# Sega_Master_System_Quick_Solder_BIOS_v1p.net
KiCad netlist of a schematic drawn in EAGLE
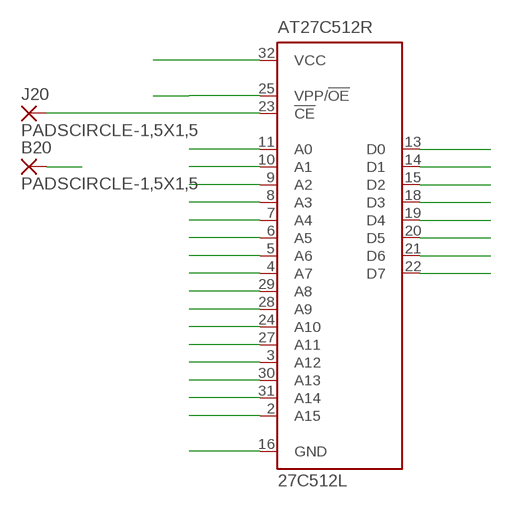
[diagram p0: schematic, sheet 1]

(export (version "E")
  (design (tool "Eeschema 10.0.6"))
  (components
    (comp (ref "AT27C512R")
      (value "27C512L")
      (footprint "eagle-import:PLCC-32")
      (fields (field (name "MPN") "M27C512-90C1"))
      (libsource (lib "eagle-import") (part "27512LC"))
    )
    (comp (ref "B20")
      (value "PADSCIRCLE-1,5X1,5")
      (footprint "eagle-import:CIRCLE-1,5X1,5")
      (libsource (lib "eagle-import") (part "PADSCIRCLE-1,5X1,5"))
    )
    (comp (ref "J20")
      (value "PADSCIRCLE-1,5X1,5")
      (footprint "eagle-import:CIRCLE-1,5X1,5")
      (libsource (lib "eagle-import") (part "PADSCIRCLE-1,5X1,5"))
    )
  )
  (nets
    (net (code "1") (name "Net-(AT27C512R-~{CE})") (class "Default")
      (node (ref "AT27C512R") (pin "23") (pinfunction "~{CE}_23") (pintype "input"))
      (node (ref "J20") (pin "1") (pinfunction "P_1") (pintype "passive"))
    )
    (net (code "2") (name "unconnected-(AT27C512R-A0-Pad11)") (class "Default")
      (node (ref "AT27C512R") (pin "11") (pinfunction "A0_11") (pintype "input"))
    )
    (net (code "3") (name "unconnected-(AT27C512R-A1-Pad10)") (class "Default")
      (node (ref "AT27C512R") (pin "10") (pinfunction "A1_10") (pintype "input"))
    )
    (net (code "4") (name "unconnected-(AT27C512R-A2-Pad9)") (class "Default")
      (node (ref "AT27C512R") (pin "9") (pinfunction "A2_9") (pintype "input"))
    )
    (net (code "5") (name "unconnected-(AT27C512R-A3-Pad8)") (class "Default")
      (node (ref "AT27C512R") (pin "8") (pinfunction "A3_8") (pintype "input"))
    )
    (net (code "6") (name "unconnected-(AT27C512R-A4-Pad7)") (class "Default")
      (node (ref "AT27C512R") (pin "7") (pinfunction "A4_7") (pintype "input"))
    )
    (net (code "7") (name "unconnected-(AT27C512R-A5-Pad6)") (class "Default")
      (node (ref "AT27C512R") (pin "6") (pinfunction "A5_6") (pintype "input"))
    )
    (net (code "8") (name "unconnected-(AT27C512R-A6-Pad5)") (class "Default")
      (node (ref "AT27C512R") (pin "5") (pinfunction "A6_5") (pintype "input"))
    )
    (net (code "9") (name "unconnected-(AT27C512R-A7-Pad4)") (class "Default")
      (node (ref "AT27C512R") (pin "4") (pinfunction "A7_4") (pintype "input"))
    )
    (net (code "10") (name "unconnected-(AT27C512R-A8-Pad29)") (class "Default")
      (node (ref "AT27C512R") (pin "29") (pinfunction "A8_29") (pintype "input"))
    )
    (net (code "11") (name "unconnected-(AT27C512R-A9-Pad28)") (class "Default")
      (node (ref "AT27C512R") (pin "28") (pinfunction "A9_28") (pintype "input"))
    )
    (net (code "12") (name "unconnected-(AT27C512R-A10-Pad24)") (class "Default")
      (node (ref "AT27C512R") (pin "24") (pinfunction "A10_24") (pintype "input"))
    )
    (net (code "13") (name "unconnected-(AT27C512R-A11-Pad27)") (class "Default")
      (node (ref "AT27C512R") (pin "27") (pinfunction "A11_27") (pintype "input"))
    )
    (net (code "14") (name "unconnected-(AT27C512R-A12-Pad3)") (class "Default")
      (node (ref "AT27C512R") (pin "3") (pinfunction "A12_3") (pintype "input"))
    )
    (net (code "15") (name "unconnected-(AT27C512R-A13-Pad30)") (class "Default")
      (node (ref "AT27C512R") (pin "30") (pinfunction "A13_30") (pintype "input"))
    )
    (net (code "16") (name "unconnected-(AT27C512R-A14-Pad31)") (class "Default")
      (node (ref "AT27C512R") (pin "31") (pinfunction "A14_31") (pintype "input"))
    )
    (net (code "17") (name "unconnected-(AT27C512R-A15-Pad2)") (class "Default")
      (node (ref "AT27C512R") (pin "2") (pinfunction "A15_2") (pintype "input"))
    )
    (net (code "18") (name "unconnected-(AT27C512R-D0-Pad13)") (class "Default")
      (node (ref "AT27C512R") (pin "13") (pinfunction "D0_13") (pintype "tri_state"))
    )
    (net (code "19") (name "unconnected-(AT27C512R-D1-Pad14)") (class "Default")
      (node (ref "AT27C512R") (pin "14") (pinfunction "D1_14") (pintype "tri_state"))
    )
    (net (code "20") (name "unconnected-(AT27C512R-D2-Pad15)") (class "Default")
      (node (ref "AT27C512R") (pin "15") (pinfunction "D2_15") (pintype "tri_state"))
    )
    (net (code "21") (name "unconnected-(AT27C512R-D3-Pad18)") (class "Default")
      (node (ref "AT27C512R") (pin "18") (pinfunction "D3_18") (pintype "tri_state"))
    )
    (net (code "22") (name "unconnected-(AT27C512R-D4-Pad19)") (class "Default")
      (node (ref "AT27C512R") (pin "19") (pinfunction "D4_19") (pintype "tri_state"))
    )
    (net (code "23") (name "unconnected-(AT27C512R-D5-Pad20)") (class "Default")
      (node (ref "AT27C512R") (pin "20") (pinfunction "D5_20") (pintype "tri_state"))
    )
    (net (code "24") (name "unconnected-(AT27C512R-D6-Pad21)") (class "Default")
      (node (ref "AT27C512R") (pin "21") (pinfunction "D6_21") (pintype "tri_state"))
    )
    (net (code "25") (name "unconnected-(AT27C512R-D7-Pad22)") (class "Default")
      (node (ref "AT27C512R") (pin "22") (pinfunction "D7_22") (pintype "tri_state"))
    )
    (net (code "26") (name "unconnected-(AT27C512R-GND-Pad16)") (class "Default")
      (node (ref "AT27C512R") (pin "16") (pinfunction "GND_16") (pintype "power_in"))
    )
    (net (code "27") (name "unconnected-(AT27C512R-VCC-Pad32)") (class "Default")
      (node (ref "AT27C512R") (pin "32") (pinfunction "VCC_32") (pintype "power_in"))
    )
    (net (code "28") (name "unconnected-(AT27C512R-VPP{slash}~{OE}-Pad25)") (class "Default")
      (node (ref "AT27C512R") (pin "25") (pinfunction "VPP/~{OE}_25") (pintype "input"))
    )
    (net (code "29") (name "unconnected-(B20-P-Pad1)") (class "Default")
      (node (ref "B20") (pin "1") (pinfunction "P_1") (pintype "passive"))
    )
  )
)
